# Spi_Flash_Smd_Programer.net
KiCad netlist of a schematic drawn in EAGLE
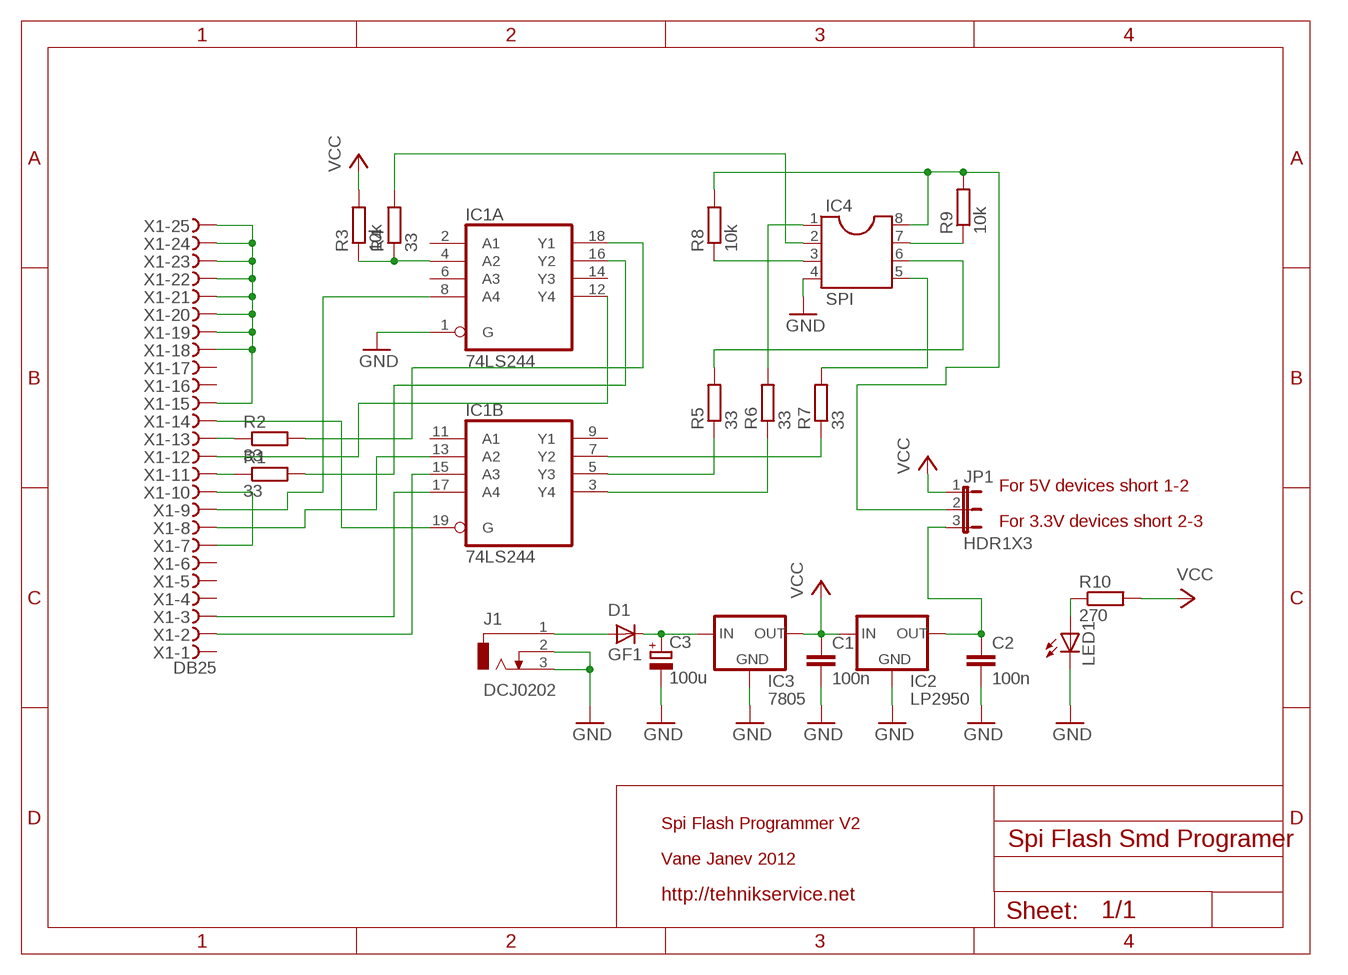
[diagram p0: schematic, sheet 1]

(export (version "E")
  (design (tool "Eeschema 10.0.6"))
  (components
    (comp (ref "C1")
      (value "100n")
      (footprint "eagle-import:C0402")
      (libsource (lib "eagle-import") (part "C-EUC0402"))
    )
    (comp (ref "C2")
      (value "100n")
      (footprint "eagle-import:C0402")
      (libsource (lib "eagle-import") (part "C-EUC0402"))
    )
    (comp (ref "C3")
      (value "100u")
      (footprint "eagle-import:150CLZ-0810")
      (libsource (lib "eagle-import") (part "CPOL-EU150CLZ-0810"))
    )
    (comp (ref "D1")
      (value "GF1")
      (footprint "eagle-import:SMA-DO214AC")
      (libsource (lib "eagle-import") (part "GF1"))
    )
    (comp (ref "IC1")
      (value "74LS244")
      (footprint "eagle-import:SO20W")
      (libsource (lib "eagle-import") (part "74244DWLS"))
    )
    (comp (ref "IC2")
      (value "LP2950")
      (footprint "eagle-import:DPACK")
      (libsource (lib "eagle-import") (part "LP2950?CDT-3.3"))
    )
    (comp (ref "IC3")
      (value "7805")
      (footprint "eagle-import:DPACK")
      (libsource (lib "eagle-import") (part "LP2950?CDT-5.0"))
    )
    (comp (ref "IC4")
      (value "SPI")
      (footprint "eagle-import:SOCKET-08")
      (libsource (lib "eagle-import") (part "DIL8S"))
    )
    (comp (ref "J1")
      (value "DCJ0202")
      (footprint "eagle-import:DCJ0202")
      (libsource (lib "eagle-import") (part "DCJ0202"))
    )
    (comp (ref "JP1")
      (value "HDR1X3")
      (footprint "eagle-import:JP2")
      (libsource (lib "eagle-import") (part "JP2E"))
    )
    (comp (ref "LED1")
      (value "LAP4-TOP")
      (footprint "eagle-import:P47F-TOP")
      (libsource (lib "eagle-import") (part "P4-TOPLA"))
    )
    (comp (ref "R1")
      (value "33")
      (footprint "eagle-import:R1005")
      (libsource (lib "eagle-import") (part "resistor_R-EU_R1005"))
    )
    (comp (ref "R2")
      (value "33")
      (footprint "eagle-import:R1005")
      (libsource (lib "eagle-import") (part "resistor_R-EU_R1005"))
    )
    (comp (ref "R3")
      (value "10k")
      (footprint "eagle-import:R1005")
      (libsource (lib "eagle-import") (part "resistor_R-EU_R1005"))
    )
    (comp (ref "R4")
      (value "33")
      (footprint "eagle-import:R1005")
      (libsource (lib "eagle-import") (part "resistor_R-EU_R1005"))
    )
    (comp (ref "R5")
      (value "33")
      (footprint "eagle-import:R1005")
      (libsource (lib "eagle-import") (part "resistor_R-EU_R1005"))
    )
    (comp (ref "R6")
      (value "33")
      (footprint "eagle-import:R1005")
      (libsource (lib "eagle-import") (part "resistor_R-EU_R1005"))
    )
    (comp (ref "R7")
      (value "33")
      (footprint "eagle-import:R1005")
      (libsource (lib "eagle-import") (part "resistor_R-EU_R1005"))
    )
    (comp (ref "R8")
      (value "10k")
      (footprint "eagle-import:R1005")
      (libsource (lib "eagle-import") (part "resistor_R-EU_R1005"))
    )
    (comp (ref "R9")
      (value "10k")
      (footprint "eagle-import:R1005")
      (libsource (lib "eagle-import") (part "resistor_R-EU_R1005"))
    )
    (comp (ref "R10")
      (value "270")
      (footprint "eagle-import:R1005")
      (libsource (lib "eagle-import") (part "R-EU_R1005"))
    )
    (comp (ref "X1")
      (value "DB25")
      (footprint "eagle-import:F25HP")
      (libsource (lib "eagle-import") (part "F25?SHP"))
    )
  )
  (nets
    (net (code "1") (name "GND") (class "Default")
      (node (ref "C1") (pin "2") (pinfunction "2_2") (pintype "passive"))
      (node (ref "C2") (pin "2") (pinfunction "2_2") (pintype "passive"))
      (node (ref "C3") (pin "-") (pinfunction "-_-") (pintype "passive"))
      (node (ref "IC1") (pin "1") (pinfunction "G_1") (pintype "input"))
      (node (ref "IC2") (pin "4") (pinfunction "GND_4") (pintype "input"))
      (node (ref "IC3") (pin "4") (pinfunction "GND_4") (pintype "input"))
      (node (ref "IC4") (pin "4") (pinfunction "4_4") (pintype "passive"))
      (node (ref "J1") (pin "2") (pinfunction "2_2") (pintype "passive"))
      (node (ref "J1") (pin "3") (pinfunction "3_3") (pintype "passive"))
      (node (ref "LED1") (pin "C") (pinfunction "C_C") (pintype "passive"))
    )
    (net (code "2") (name "Net-(D1-C)") (class "Default")
      (node (ref "C3") (pin "+") (pinfunction "+_+") (pintype "passive"))
      (node (ref "D1") (pin "K") (pinfunction "C_K") (pintype "passive"))
      (node (ref "IC3") (pin "1") (pinfunction "IN_1") (pintype "input"))
    )
    (net (code "3") (name "Net-(D1-PadA)") (class "Default")
      (node (ref "D1") (pin "A") (pinfunction "A_A") (pintype "passive"))
      (node (ref "J1") (pin "1") (pinfunction "1_1") (pintype "passive"))
    )
    (net (code "4") (name "Net-(IC1A-A2)") (class "Default")
      (node (ref "IC1") (pin "4") (pinfunction "A2_4") (pintype "input"))
      (node (ref "R3") (pin "1") (pinfunction "1_1") (pintype "passive"))
      (node (ref "R4") (pin "1") (pinfunction "1_1") (pintype "passive"))
    )
    (net (code "5") (name "Net-(IC1A-A4)") (class "Default")
      (node (ref "IC1") (pin "8") (pinfunction "A4_8") (pintype "input"))
      (node (ref "X1") (pin "9") (pinfunction "F_9") (pintype "passive"))
    )
    (net (code "6") (name "Net-(IC1A-Y1)") (class "Default")
      (node (ref "IC1") (pin "18") (pinfunction "Y1_18") (pintype "tri_state"))
      (node (ref "R2") (pin "2") (pinfunction "2_2") (pintype "passive"))
    )
    (net (code "7") (name "Net-(IC1A-Y2)") (class "Default")
      (node (ref "IC1") (pin "16") (pinfunction "Y2_16") (pintype "tri_state"))
      (node (ref "R1") (pin "2") (pinfunction "2_2") (pintype "passive"))
    )
    (net (code "8") (name "Net-(IC1A-Y4)") (class "Default")
      (node (ref "IC1") (pin "12") (pinfunction "Y4_12") (pintype "tri_state"))
      (node (ref "X1") (pin "12") (pinfunction "F_12") (pintype "passive"))
    )
    (net (code "9") (name "Net-(IC1B-A2)") (class "Default")
      (node (ref "IC1") (pin "13") (pinfunction "A2_13") (pintype "input"))
      (node (ref "X1") (pin "8") (pinfunction "F_8") (pintype "passive"))
    )
    (net (code "10") (name "Net-(IC1B-A3)") (class "Default")
      (node (ref "IC1") (pin "15") (pinfunction "A3_15") (pintype "input"))
      (node (ref "X1") (pin "2") (pinfunction "F_2") (pintype "passive"))
    )
    (net (code "11") (name "Net-(IC1B-A4)") (class "Default")
      (node (ref "IC1") (pin "17") (pinfunction "A4_17") (pintype "input"))
      (node (ref "X1") (pin "3") (pinfunction "F_3") (pintype "passive"))
    )
    (net (code "12") (name "Net-(IC1B-G)") (class "Default")
      (node (ref "IC1") (pin "19") (pinfunction "G_19") (pintype "input"))
      (node (ref "X1") (pin "14") (pinfunction "F_14") (pintype "passive"))
    )
    (net (code "13") (name "Net-(IC1B-Y2)") (class "Default")
      (node (ref "IC1") (pin "7") (pinfunction "Y2_7") (pintype "tri_state"))
      (node (ref "R7") (pin "1") (pinfunction "1_1") (pintype "passive"))
    )
    (net (code "14") (name "Net-(IC1B-Y3)") (class "Default")
      (node (ref "IC1") (pin "5") (pinfunction "Y3_5") (pintype "tri_state"))
      (node (ref "R5") (pin "1") (pinfunction "1_1") (pintype "passive"))
    )
    (net (code "15") (name "Net-(IC1B-Y4)") (class "Default")
      (node (ref "IC1") (pin "3") (pinfunction "Y4_3") (pintype "tri_state"))
      (node (ref "R6") (pin "1") (pinfunction "1_1") (pintype "passive"))
    )
    (net (code "16") (name "Net-(IC2-OUT)") (class "Default")
      (node (ref "C2") (pin "1") (pinfunction "1_1") (pintype "passive"))
      (node (ref "IC2") (pin "3") (pinfunction "OUT_3") (pintype "passive"))
      (node (ref "JP1") (pin "3") (pinfunction "3_3") (pintype "passive"))
    )
    (net (code "17") (name "Net-(IC4-Pad1)") (class "Default")
      (node (ref "IC4") (pin "1") (pinfunction "1_1") (pintype "passive"))
      (node (ref "R6") (pin "2") (pinfunction "2_2") (pintype "passive"))
    )
    (net (code "18") (name "Net-(IC4-Pad2)") (class "Default")
      (node (ref "IC4") (pin "2") (pinfunction "2_2") (pintype "passive"))
      (node (ref "R4") (pin "2") (pinfunction "2_2") (pintype "passive"))
    )
    (net (code "19") (name "Net-(IC4-Pad3)") (class "Default")
      (node (ref "IC4") (pin "3") (pinfunction "3_3") (pintype "passive"))
      (node (ref "R8") (pin "1") (pinfunction "1_1") (pintype "passive"))
    )
    (net (code "20") (name "Net-(IC4-Pad5)") (class "Default")
      (node (ref "IC4") (pin "5") (pinfunction "5_5") (pintype "passive"))
      (node (ref "R7") (pin "2") (pinfunction "2_2") (pintype "passive"))
    )
    (net (code "21") (name "Net-(IC4-Pad6)") (class "Default")
      (node (ref "IC4") (pin "6") (pinfunction "6_6") (pintype "passive"))
      (node (ref "R5") (pin "2") (pinfunction "2_2") (pintype "passive"))
    )
    (net (code "22") (name "Net-(IC4-Pad7)") (class "Default")
      (node (ref "IC4") (pin "7") (pinfunction "7_7") (pintype "passive"))
      (node (ref "R9") (pin "1") (pinfunction "1_1") (pintype "passive"))
    )
    (net (code "23") (name "Net-(IC4-Pad8)") (class "Default")
      (node (ref "IC4") (pin "8") (pinfunction "8_8") (pintype "passive"))
      (node (ref "JP1") (pin "2") (pinfunction "2_2") (pintype "passive"))
      (node (ref "R8") (pin "2") (pinfunction "2_2") (pintype "passive"))
      (node (ref "R9") (pin "2") (pinfunction "2_2") (pintype "passive"))
    )
    (net (code "24") (name "Net-(LED1-PadA)") (class "Default")
      (node (ref "LED1") (pin "A") (pinfunction "A_A") (pintype "passive"))
      (node (ref "R10") (pin "1") (pinfunction "1_1") (pintype "passive"))
    )
    (net (code "25") (name "Net-(X1B-F)") (class "Default")
      (node (ref "X1") (pin "10") (pinfunction "F_10") (pintype "passive"))
      (node (ref "X1") (pin "7") (pinfunction "F_7") (pintype "passive"))
    )
    (net (code "26") (name "Net-(X1C-F)") (class "Default")
      (node (ref "R1") (pin "1") (pinfunction "1_1") (pintype "passive"))
      (node (ref "X1") (pin "11") (pinfunction "F_11") (pintype "passive"))
    )
    (net (code "27") (name "Net-(X1E-F)") (class "Default")
      (node (ref "R2") (pin "1") (pinfunction "1_1") (pintype "passive"))
      (node (ref "X1") (pin "13") (pinfunction "F_13") (pintype "passive"))
    )
    (net (code "28") (name "Net-(X1G-F)") (class "Default")
      (node (ref "X1") (pin "15") (pinfunction "F_15") (pintype "passive"))
      (node (ref "X1") (pin "18") (pinfunction "F_18") (pintype "passive"))
      (node (ref "X1") (pin "19") (pinfunction "F_19") (pintype "passive"))
      (node (ref "X1") (pin "20") (pinfunction "F_20") (pintype "passive"))
      (node (ref "X1") (pin "21") (pinfunction "F_21") (pintype "passive"))
      (node (ref "X1") (pin "22") (pinfunction "F_22") (pintype "passive"))
      (node (ref "X1") (pin "23") (pinfunction "F_23") (pintype "passive"))
      (node (ref "X1") (pin "24") (pinfunction "F_24") (pintype "passive"))
      (node (ref "X1") (pin "25") (pinfunction "F_25") (pintype "passive"))
    )
    (net (code "29") (name "VCC") (class "Default")
      (node (ref "C1") (pin "1") (pinfunction "1_1") (pintype "passive"))
      (node (ref "IC2") (pin "1") (pinfunction "IN_1") (pintype "input"))
      (node (ref "IC3") (pin "3") (pinfunction "OUT_3") (pintype "passive"))
      (node (ref "JP1") (pin "1") (pinfunction "1_1") (pintype "passive"))
      (node (ref "R10") (pin "2") (pinfunction "2_2") (pintype "passive"))
      (node (ref "R3") (pin "2") (pinfunction "2_2") (pintype "passive"))
    )
    (net (code "30") (name "unconnected-(IC1A-A1-Pad2)") (class "Default")
      (node (ref "IC1") (pin "2") (pinfunction "A1_2") (pintype "input"))
    )
    (net (code "31") (name "unconnected-(IC1A-A3-Pad6)") (class "Default")
      (node (ref "IC1") (pin "6") (pinfunction "A3_6") (pintype "input"))
    )
    (net (code "32") (name "unconnected-(IC1A-Y3-Pad14)") (class "Default")
      (node (ref "IC1") (pin "14") (pinfunction "Y3_14") (pintype "tri_state"))
    )
    (net (code "33") (name "unconnected-(IC1B-A1-Pad11)") (class "Default")
      (node (ref "IC1") (pin "11") (pinfunction "A1_11") (pintype "input"))
    )
    (net (code "34") (name "unconnected-(IC1B-Y1-Pad9)") (class "Default")
      (node (ref "IC1") (pin "9") (pinfunction "Y1_9") (pintype "tri_state"))
    )
    (net (code "35") (name "unconnected-(X1A-F-Pad1)") (class "Default")
      (node (ref "X1") (pin "1") (pinfunction "F_1") (pintype "passive"))
    )
    (net (code "36") (name "unconnected-(X1H-F-Pad16)") (class "Default")
      (node (ref "X1") (pin "16") (pinfunction "F_16") (pintype "passive"))
    )
    (net (code "37") (name "unconnected-(X1I-F-Pad17)") (class "Default")
      (node (ref "X1") (pin "17") (pinfunction "F_17") (pintype "passive"))
    )
    (net (code "38") (name "unconnected-(X1T-F-Pad4)") (class "Default")
      (node (ref "X1") (pin "4") (pinfunction "F_4") (pintype "passive"))
    )
    (net (code "39") (name "unconnected-(X1U-F-Pad5)") (class "Default")
      (node (ref "X1") (pin "5") (pinfunction "F_5") (pintype "passive"))
    )
    (net (code "40") (name "unconnected-(X1V-F-Pad6)") (class "Default")
      (node (ref "X1") (pin "6") (pinfunction "F_6") (pintype "passive"))
    )
  )
)
